# SCH_AC400-Controller_2024-03-15.net
KiCad netlist of a schematic drawn in EasyEDA
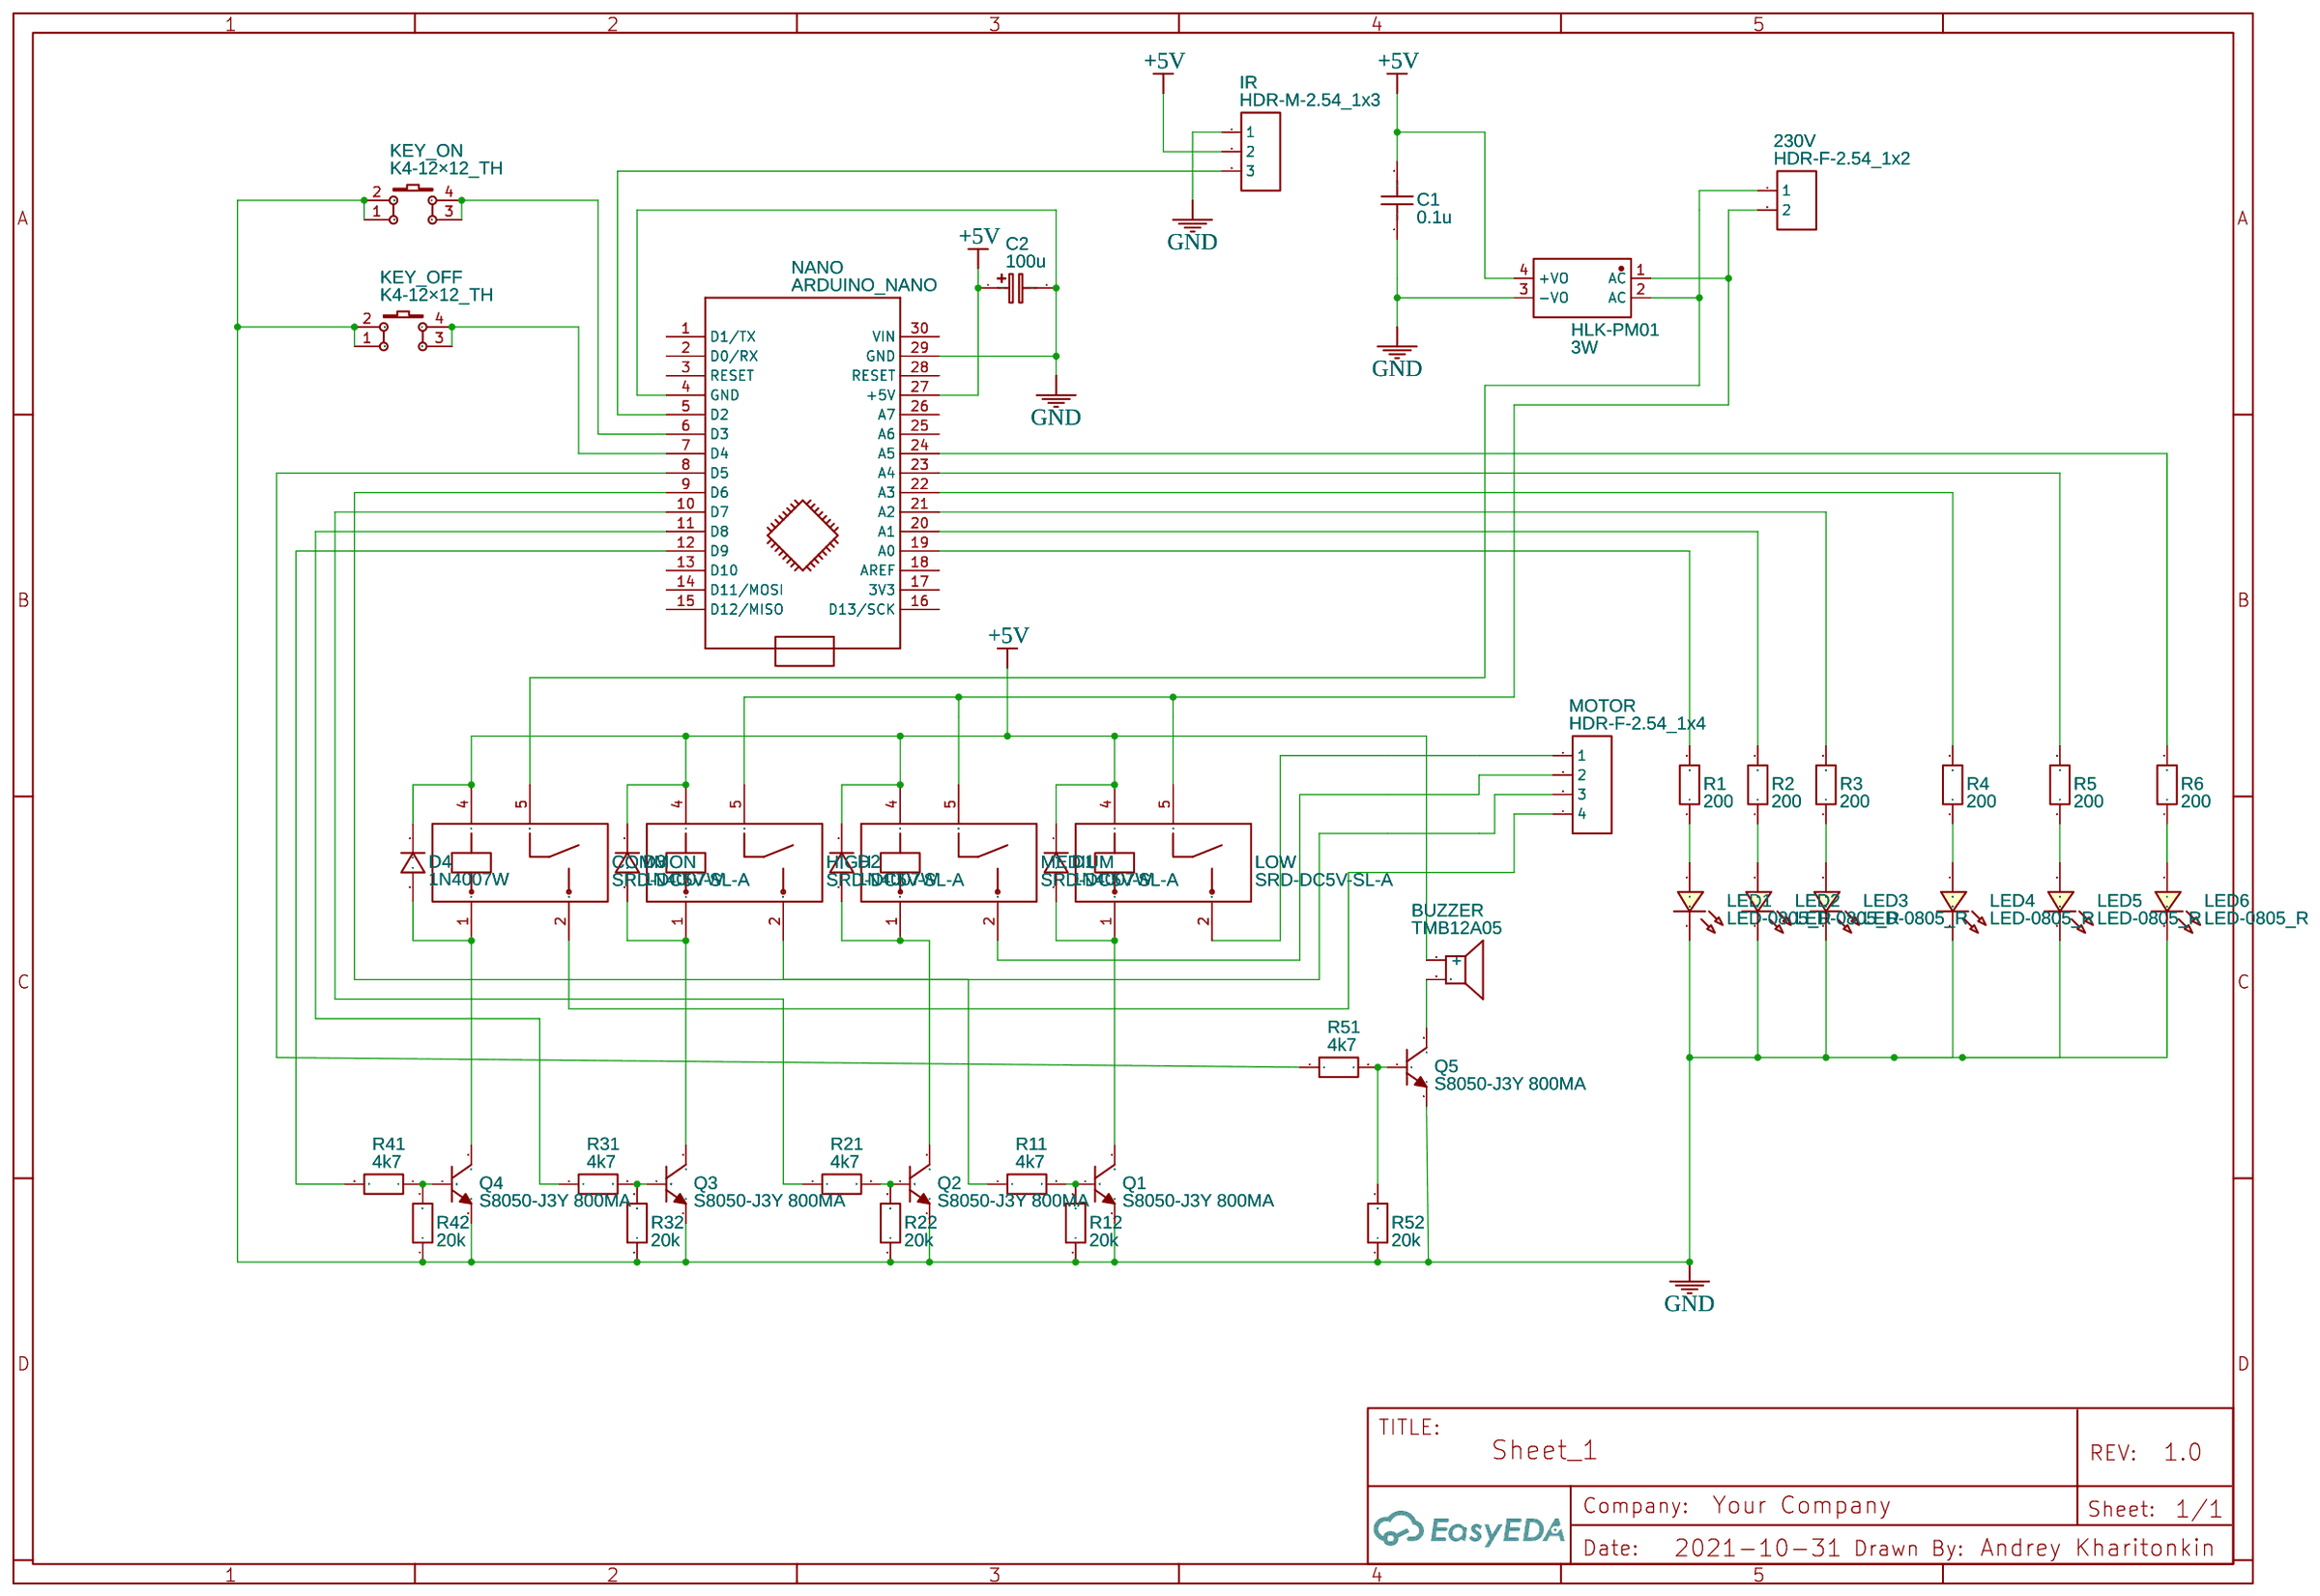
[diagram p0: schematic sheet]

(export (version "E")
  (design (tool "Eeschema 10.0.6"))
  (components
    (comp (ref "3W")
      (value "HLK-PM01")
      (fields (field (name "Manufacturer") "HI-LINK"))
      (libsource (lib "") (part "HLK-PM01"))
    )
    (comp (ref "230V") (value "HDR-F-2.54_1x2") (libsource (lib "") (part "HDR-F-2.54_1x2")))
    (comp (ref "BUZZER")
      (value "TMB12A05")
      (fields (field (name "Manufacturer") "HNDZ"))
      (libsource (lib "") (part "TMB12A05"))
    )
    (comp (ref "C1")
      (value "0.1u")
      (fields
        (field (name "Manufacturer Part") "CT41G-0805-2X1-50V-0.1uF-K(N)")
        (field (name "Manufacturer") "TORCH")
      )
      (libsource (lib "") (part "C_1206_US"))
    )
    (comp (ref "C2") (value "100u") (libsource (lib "") (part "CE_TH_D6.3×F2.5_EU")))
    (comp (ref "COMMON")
      (value "SRD-DC5V-SL-A")
      (fields (field (name "Manufacturer") "Ningbo Songle Relay"))
      (libsource (lib "") (part "SRD-DC5V-SL-A"))
    )
    (comp (ref "D1")
      (value "1N4007W")
      (fields (field (name "Manufacturer") "BLUE ROCKET"))
      (libsource (lib "") (part "1N4007W"))
    )
    (comp (ref "D2")
      (value "1N4007W")
      (fields (field (name "Manufacturer") "BLUE ROCKET"))
      (libsource (lib "") (part "1N4007W"))
    )
    (comp (ref "D3")
      (value "1N4007W")
      (fields (field (name "Manufacturer") "BLUE ROCKET"))
      (libsource (lib "") (part "1N4007W"))
    )
    (comp (ref "D4")
      (value "1N4007W")
      (fields (field (name "Manufacturer") "BLUE ROCKET"))
      (libsource (lib "") (part "1N4007W"))
    )
    (comp (ref "HIGH")
      (value "SRD-DC5V-SL-A")
      (fields (field (name "Manufacturer") "Ningbo Songle Relay"))
      (libsource (lib "") (part "SRD-DC5V-SL-A_1"))
    )
    (comp (ref "IR") (value "HDR-M-2.54_1x3") (libsource (lib "") (part "HDR-M-2.54_1x3")))
    (comp (ref "KEY_OFF")
      (value "K4-12×12_TH")
      (fields (field (name "Manufacturer Part") "K2-1103DP-M4SW-04") (field (name "Manufacturer") "韩国韩荣"))
      (libsource (lib "") (part "K4-12×12_TH"))
    )
    (comp (ref "KEY_ON")
      (value "K4-12×12_TH")
      (fields (field (name "Manufacturer Part") "K2-1103DP-M4SW-04") (field (name "Manufacturer") "韩国韩荣"))
      (libsource (lib "") (part "K4-12×12_TH_1"))
    )
    (comp (ref "LED1")
      (value "LED-0805_R")
      (fields
        (field (name "Manufacturer Part") "17-21SURC/S530-A3/TR8")
        (field (name "Manufacturer") "EVERLIGHT(台湾亿光)")
      )
      (libsource (lib "") (part "LED-0805_R"))
    )
    (comp (ref "LED2")
      (value "LED-0805_R")
      (fields
        (field (name "Manufacturer Part") "17-21SURC/S530-A3/TR8")
        (field (name "Manufacturer") "EVERLIGHT(台湾亿光)")
      )
      (libsource (lib "") (part "LED-0805_R"))
    )
    (comp (ref "LED3")
      (value "LED-0805_R")
      (fields
        (field (name "Manufacturer Part") "17-21SURC/S530-A3/TR8")
        (field (name "Manufacturer") "EVERLIGHT(台湾亿光)")
      )
      (libsource (lib "") (part "LED-0805_R"))
    )
    (comp (ref "LED4")
      (value "LED-0805_R")
      (fields
        (field (name "Manufacturer Part") "17-21SURC/S530-A3/TR8")
        (field (name "Manufacturer") "EVERLIGHT(台湾亿光)")
      )
      (libsource (lib "") (part "LED-0805_R"))
    )
    (comp (ref "LED5")
      (value "LED-0805_R")
      (fields
        (field (name "Manufacturer Part") "17-21SURC/S530-A3/TR8")
        (field (name "Manufacturer") "EVERLIGHT(台湾亿光)")
      )
      (libsource (lib "") (part "LED-0805_R"))
    )
    (comp (ref "LED6")
      (value "LED-0805_R")
      (fields
        (field (name "Manufacturer Part") "17-21SURC/S530-A3/TR8")
        (field (name "Manufacturer") "EVERLIGHT(台湾亿光)")
      )
      (libsource (lib "") (part "LED-0805_R"))
    )
    (comp (ref "LOW")
      (value "SRD-DC5V-SL-A")
      (fields (field (name "Manufacturer") "Ningbo Songle Relay"))
      (libsource (lib "") (part "SRD-DC5V-SL-A_2"))
    )
    (comp (ref "MEDIUM")
      (value "SRD-DC5V-SL-A")
      (fields (field (name "Manufacturer") "Ningbo Songle Relay"))
      (libsource (lib "") (part "SRD-DC5V-SL-A_3"))
    )
    (comp (ref "MOTOR") (value "HDR-F-2.54_1x4") (libsource (lib "") (part "HDR-F-2.54_1x4")))
    (comp (ref "NANO")
      (value "ARDUINO_NANO")
      (fields (field (name "Manufacturer Part") "?"))
      (libsource (lib "") (part "Unknown_405_-570"))
    )
    (comp (ref "Q1")
      (value "S8050-J3Y 800MA")
      (fields (field (name "Manufacturer") "IDCHIP(英锐芯)"))
      (libsource (lib "") (part "S8050-J3Y 800MA"))
    )
    (comp (ref "Q2")
      (value "S8050-J3Y 800MA")
      (fields (field (name "Manufacturer") "IDCHIP(英锐芯)"))
      (libsource (lib "") (part "S8050-J3Y 800MA"))
    )
    (comp (ref "Q3")
      (value "S8050-J3Y 800MA")
      (fields (field (name "Manufacturer") "IDCHIP(英锐芯)"))
      (libsource (lib "") (part "S8050-J3Y 800MA"))
    )
    (comp (ref "Q4")
      (value "S8050-J3Y 800MA")
      (fields (field (name "Manufacturer") "IDCHIP(英锐芯)"))
      (libsource (lib "") (part "S8050-J3Y 800MA"))
    )
    (comp (ref "Q5")
      (value "S8050-J3Y 800MA")
      (fields (field (name "Manufacturer") "IDCHIP(英锐芯)"))
      (libsource (lib "") (part "S8050-J3Y 800MA"))
    )
    (comp (ref "R1")
      (value "200")
      (fields (field (name "Manufacturer Part") "0805W8F2000T5E") (field (name "Manufacturer") "UniOhm"))
      (libsource (lib "") (part "R_0805_EU_1"))
    )
    (comp (ref "R2")
      (value "200")
      (fields (field (name "Manufacturer Part") "0805W8F2000T5E") (field (name "Manufacturer") "UniOhm"))
      (libsource (lib "") (part "R_0805_EU_1"))
    )
    (comp (ref "R3")
      (value "200")
      (fields (field (name "Manufacturer Part") "0805W8F2000T5E") (field (name "Manufacturer") "UniOhm"))
      (libsource (lib "") (part "R_0805_EU_1"))
    )
    (comp (ref "R4")
      (value "200")
      (fields (field (name "Manufacturer Part") "0805W8F2000T5E") (field (name "Manufacturer") "UniOhm"))
      (libsource (lib "") (part "R_0805_EU_1"))
    )
    (comp (ref "R5")
      (value "200")
      (fields (field (name "Manufacturer Part") "0805W8F2000T5E") (field (name "Manufacturer") "UniOhm"))
      (libsource (lib "") (part "R_0805_EU_1"))
    )
    (comp (ref "R6")
      (value "200")
      (fields (field (name "Manufacturer Part") "0805W8F2000T5E") (field (name "Manufacturer") "UniOhm"))
      (libsource (lib "") (part "R_0805_EU_1"))
    )
    (comp (ref "R11") (value "4k7") (libsource (lib "") (part "R_0805_EU_2")))
    (comp (ref "R12") (value "20k") (libsource (lib "") (part "R_0805_EU_1")))
    (comp (ref "R21") (value "4k7") (libsource (lib "") (part "R_0805_EU_2")))
    (comp (ref "R22") (value "20k") (libsource (lib "") (part "R_0805_EU_1")))
    (comp (ref "R31") (value "4k7") (libsource (lib "") (part "R_0805_EU_2")))
    (comp (ref "R32") (value "20k") (libsource (lib "") (part "R_0805_EU_1")))
    (comp (ref "R41") (value "4k7") (libsource (lib "") (part "R_0805_EU")))
    (comp (ref "R42") (value "20k") (libsource (lib "") (part "R_0805_EU_1")))
    (comp (ref "R51") (value "4k7") (libsource (lib "") (part "R_0805_EU_2")))
    (comp (ref "R52") (value "20k") (libsource (lib "") (part "R_0805_EU_1")))
  )
  (nets
    (net (code "1") (name "+5V") (class "Default")
      (node (ref "3W") (pin "4") (pinfunction "+VO_4") (pintype "unspecified"))
      (node (ref "BUZZER") (pin "1") (pinfunction "+_1") (pintype "unspecified"))
      (node (ref "C1") (pin "2") (pinfunction "2_2") (pintype "unspecified"))
      (node (ref "C2") (pin "1") (pinfunction "1_1") (pintype "unspecified"))
      (node (ref "COMMON") (pin "4") (pinfunction "4_4") (pintype "input"))
      (node (ref "D1") (pin "1") (pinfunction "1_1") (pintype "unspecified"))
      (node (ref "D2") (pin "1") (pinfunction "1_1") (pintype "unspecified"))
      (node (ref "D3") (pin "1") (pinfunction "1_1") (pintype "unspecified"))
      (node (ref "D4") (pin "1") (pinfunction "1_1") (pintype "unspecified"))
      (node (ref "HIGH") (pin "4") (pinfunction "4_4") (pintype "input"))
      (node (ref "IR") (pin "2") (pinfunction "2_2") (pintype "input"))
      (node (ref "LOW") (pin "4") (pinfunction "4_4") (pintype "input"))
      (node (ref "MEDIUM") (pin "4") (pinfunction "4_4") (pintype "input"))
      (node (ref "NANO") (pin "27") (pinfunction "+5V_27") (pintype "unspecified"))
    )
    (net (code "2") (name "GND") (class "Default")
      (node (ref "3W") (pin "3") (pinfunction "-VO_3") (pintype "unspecified"))
      (node (ref "C1") (pin "1") (pinfunction "1_1") (pintype "unspecified"))
      (node (ref "C2") (pin "2") (pinfunction "2_2") (pintype "unspecified"))
      (node (ref "IR") (pin "1") (pinfunction "1_1") (pintype "input"))
      (node (ref "KEY_OFF") (pin "1") (pinfunction "1_1") (pintype "unspecified"))
      (node (ref "KEY_OFF") (pin "2") (pinfunction "2_2") (pintype "unspecified"))
      (node (ref "KEY_ON") (pin "1") (pinfunction "1_1") (pintype "unspecified"))
      (node (ref "KEY_ON") (pin "2") (pinfunction "2_2") (pintype "unspecified"))
      (node (ref "LED1") (pin "2") (pinfunction "2_2") (pintype "unspecified"))
      (node (ref "LED2") (pin "2") (pinfunction "2_2") (pintype "unspecified"))
      (node (ref "LED3") (pin "2") (pinfunction "2_2") (pintype "unspecified"))
      (node (ref "LED4") (pin "2") (pinfunction "2_2") (pintype "unspecified"))
      (node (ref "LED5") (pin "2") (pinfunction "2_2") (pintype "unspecified"))
      (node (ref "LED6") (pin "2") (pinfunction "2_2") (pintype "unspecified"))
      (node (ref "NANO") (pin "29") (pinfunction "GND_29") (pintype "unspecified"))
      (node (ref "NANO") (pin "4") (pinfunction "GND_4") (pintype "unspecified"))
      (node (ref "Q1") (pin "2") (pinfunction "E_2") (pintype "input"))
      (node (ref "Q2") (pin "2") (pinfunction "E_2") (pintype "input"))
      (node (ref "Q3") (pin "2") (pinfunction "E_2") (pintype "input"))
      (node (ref "Q4") (pin "2") (pinfunction "E_2") (pintype "input"))
      (node (ref "Q5") (pin "2") (pinfunction "E_2") (pintype "input"))
      (node (ref "R12") (pin "1") (pinfunction "1_1") (pintype "unspecified"))
      (node (ref "R22") (pin "1") (pinfunction "1_1") (pintype "unspecified"))
      (node (ref "R32") (pin "1") (pinfunction "1_1") (pintype "unspecified"))
      (node (ref "R42") (pin "1") (pinfunction "1_1") (pintype "unspecified"))
      (node (ref "R52") (pin "1") (pinfunction "1_1") (pintype "unspecified"))
    )
    (net (code "3") (name "Net-(230V-Pad1)") (class "Default")
      (node (ref "230V") (pin "1") (pinfunction "1_1") (pintype "input"))
      (node (ref "3W") (pin "2") (pinfunction "AC_2") (pintype "unspecified"))
      (node (ref "COMMON") (pin "5") (pinfunction "5_5") (pintype "input"))
    )
    (net (code "4") (name "Net-(230V-Pad2)") (class "Default")
      (node (ref "230V") (pin "2") (pinfunction "2_2") (pintype "input"))
      (node (ref "3W") (pin "1") (pinfunction "AC_1") (pintype "unspecified"))
      (node (ref "HIGH") (pin "5") (pinfunction "5_5") (pintype "input"))
      (node (ref "LOW") (pin "5") (pinfunction "5_5") (pintype "input"))
      (node (ref "MEDIUM") (pin "5") (pinfunction "5_5") (pintype "input"))
    )
    (net (code "5") (name "Net-(COMMON-Pad2)") (class "Default")
      (node (ref "COMMON") (pin "2") (pinfunction "2_2") (pintype "input"))
      (node (ref "MOTOR") (pin "4") (pinfunction "4_4") (pintype "unspecified"))
    )
    (net (code "6") (name "Net-(HIGH-Pad2)") (class "Default")
      (node (ref "HIGH") (pin "2") (pinfunction "2_2") (pintype "input"))
      (node (ref "MOTOR") (pin "3") (pinfunction "3_3") (pintype "unspecified"))
    )
    (net (code "7") (name "Net-(LED1-Pad1)") (class "Default")
      (node (ref "LED1") (pin "1") (pinfunction "1_1") (pintype "unspecified"))
      (node (ref "R1") (pin "1") (pinfunction "1_1") (pintype "unspecified"))
    )
    (net (code "8") (name "Net-(LED2-Pad1)") (class "Default")
      (node (ref "LED2") (pin "1") (pinfunction "1_1") (pintype "unspecified"))
      (node (ref "R2") (pin "1") (pinfunction "1_1") (pintype "unspecified"))
    )
    (net (code "9") (name "Net-(LED3-Pad1)") (class "Default")
      (node (ref "LED3") (pin "1") (pinfunction "1_1") (pintype "unspecified"))
      (node (ref "R3") (pin "1") (pinfunction "1_1") (pintype "unspecified"))
    )
    (net (code "10") (name "Net-(LED4-Pad1)") (class "Default")
      (node (ref "LED4") (pin "1") (pinfunction "1_1") (pintype "unspecified"))
      (node (ref "R4") (pin "1") (pinfunction "1_1") (pintype "unspecified"))
    )
    (net (code "11") (name "Net-(LED5-Pad1)") (class "Default")
      (node (ref "LED5") (pin "1") (pinfunction "1_1") (pintype "unspecified"))
      (node (ref "R5") (pin "1") (pinfunction "1_1") (pintype "unspecified"))
    )
    (net (code "12") (name "Net-(LED6-Pad1)") (class "Default")
      (node (ref "LED6") (pin "1") (pinfunction "1_1") (pintype "unspecified"))
      (node (ref "R6") (pin "1") (pinfunction "1_1") (pintype "unspecified"))
    )
    (net (code "13") (name "Net-(LOW-Pad2)") (class "Default")
      (node (ref "LOW") (pin "2") (pinfunction "2_2") (pintype "input"))
      (node (ref "MOTOR") (pin "1") (pinfunction "1_1") (pintype "unspecified"))
    )
    (net (code "14") (name "Net-(MEDIUM-Pad2)") (class "Default")
      (node (ref "MEDIUM") (pin "2") (pinfunction "2_2") (pintype "input"))
      (node (ref "MOTOR") (pin "2") (pinfunction "2_2") (pintype "unspecified"))
    )
    (net (code "15") (name "Net-(NANO-A0)") (class "Default")
      (node (ref "NANO") (pin "19") (pinfunction "A0_19") (pintype "unspecified"))
      (node (ref "R1") (pin "2") (pinfunction "2_2") (pintype "unspecified"))
    )
    (net (code "16") (name "Net-(NANO-A1)") (class "Default")
      (node (ref "NANO") (pin "20") (pinfunction "A1_20") (pintype "unspecified"))
      (node (ref "R2") (pin "2") (pinfunction "2_2") (pintype "unspecified"))
    )
    (net (code "17") (name "Net-(NANO-A2)") (class "Default")
      (node (ref "NANO") (pin "21") (pinfunction "A2_21") (pintype "unspecified"))
      (node (ref "R3") (pin "2") (pinfunction "2_2") (pintype "unspecified"))
    )
    (net (code "18") (name "Net-(NANO-A3)") (class "Default")
      (node (ref "NANO") (pin "22") (pinfunction "A3_22") (pintype "unspecified"))
      (node (ref "R4") (pin "2") (pinfunction "2_2") (pintype "unspecified"))
    )
    (net (code "19") (name "Net-(NANO-A4)") (class "Default")
      (node (ref "NANO") (pin "23") (pinfunction "A4_23") (pintype "unspecified"))
      (node (ref "R5") (pin "2") (pinfunction "2_2") (pintype "unspecified"))
    )
    (net (code "20") (name "Net-(NANO-A5)") (class "Default")
      (node (ref "NANO") (pin "24") (pinfunction "A5_24") (pintype "unspecified"))
      (node (ref "R6") (pin "2") (pinfunction "2_2") (pintype "unspecified"))
    )
    (net (code "21") (name "Net-(NANO-D2)") (class "Default")
      (node (ref "IR") (pin "3") (pinfunction "3_3") (pintype "input"))
      (node (ref "NANO") (pin "5") (pinfunction "D2_5") (pintype "unspecified"))
    )
    (net (code "22") (name "Net-(NANO-D3)") (class "Default")
      (node (ref "KEY_ON") (pin "3") (pinfunction "3_3") (pintype "unspecified"))
      (node (ref "KEY_ON") (pin "4") (pinfunction "4_4") (pintype "unspecified"))
      (node (ref "NANO") (pin "6") (pinfunction "D3_6") (pintype "unspecified"))
    )
    (net (code "23") (name "Net-(NANO-D4)") (class "Default")
      (node (ref "KEY_OFF") (pin "3") (pinfunction "3_3") (pintype "unspecified"))
      (node (ref "KEY_OFF") (pin "4") (pinfunction "4_4") (pintype "unspecified"))
      (node (ref "NANO") (pin "7") (pinfunction "D4_7") (pintype "unspecified"))
    )
    (net (code "24") (name "Net-(NANO-D5)") (class "Default")
      (node (ref "NANO") (pin "8") (pinfunction "D5_8") (pintype "unspecified"))
      (node (ref "R51") (pin "1") (pinfunction "1_1") (pintype "unspecified"))
    )
    (net (code "25") (name "Net-(NANO-D6)") (class "Default")
      (node (ref "NANO") (pin "9") (pinfunction "D6_9") (pintype "unspecified"))
      (node (ref "R11") (pin "1") (pinfunction "1_1") (pintype "unspecified"))
    )
    (net (code "26") (name "Net-(NANO-D7)") (class "Default")
      (node (ref "NANO") (pin "10") (pinfunction "D7_10") (pintype "unspecified"))
      (node (ref "R21") (pin "1") (pinfunction "1_1") (pintype "unspecified"))
    )
    (net (code "27") (name "Net-(NANO-D8)") (class "Default")
      (node (ref "NANO") (pin "11") (pinfunction "D8_11") (pintype "unspecified"))
      (node (ref "R31") (pin "1") (pinfunction "1_1") (pintype "unspecified"))
    )
    (net (code "28") (name "Net-(NANO-D9)") (class "Default")
      (node (ref "NANO") (pin "12") (pinfunction "D9_12") (pintype "unspecified"))
      (node (ref "R41") (pin "2") (pinfunction "2_2") (pintype "unspecified"))
    )
    (net (code "29") (name "Net-(Q1-B)") (class "Default")
      (node (ref "Q1") (pin "1") (pinfunction "B_1") (pintype "input"))
      (node (ref "R11") (pin "2") (pinfunction "2_2") (pintype "unspecified"))
      (node (ref "R12") (pin "2") (pinfunction "2_2") (pintype "unspecified"))
    )
    (net (code "30") (name "Net-(Q1-C)") (class "Default")
      (node (ref "D1") (pin "2") (pinfunction "2_2") (pintype "unspecified"))
      (node (ref "LOW") (pin "1") (pinfunction "1_1") (pintype "input"))
      (node (ref "Q1") (pin "3") (pinfunction "C_3") (pintype "input"))
    )
    (net (code "31") (name "Net-(Q2-B)") (class "Default")
      (node (ref "Q2") (pin "1") (pinfunction "B_1") (pintype "input"))
      (node (ref "R21") (pin "2") (pinfunction "2_2") (pintype "unspecified"))
      (node (ref "R22") (pin "2") (pinfunction "2_2") (pintype "unspecified"))
    )
    (net (code "32") (name "Net-(Q2-C)") (class "Default")
      (node (ref "D2") (pin "2") (pinfunction "2_2") (pintype "unspecified"))
      (node (ref "MEDIUM") (pin "1") (pinfunction "1_1") (pintype "input"))
      (node (ref "Q2") (pin "3") (pinfunction "C_3") (pintype "input"))
    )
    (net (code "33") (name "Net-(Q3-B)") (class "Default")
      (node (ref "Q3") (pin "1") (pinfunction "B_1") (pintype "input"))
      (node (ref "R31") (pin "2") (pinfunction "2_2") (pintype "unspecified"))
      (node (ref "R32") (pin "2") (pinfunction "2_2") (pintype "unspecified"))
    )
    (net (code "34") (name "Net-(Q3-C)") (class "Default")
      (node (ref "D3") (pin "2") (pinfunction "2_2") (pintype "unspecified"))
      (node (ref "HIGH") (pin "1") (pinfunction "1_1") (pintype "input"))
      (node (ref "Q3") (pin "3") (pinfunction "C_3") (pintype "input"))
    )
    (net (code "35") (name "Net-(Q4-B)") (class "Default")
      (node (ref "Q4") (pin "1") (pinfunction "B_1") (pintype "input"))
      (node (ref "R41") (pin "1") (pinfunction "1_1") (pintype "unspecified"))
      (node (ref "R42") (pin "2") (pinfunction "2_2") (pintype "unspecified"))
    )
    (net (code "36") (name "Net-(Q4-C)") (class "Default")
      (node (ref "COMMON") (pin "1") (pinfunction "1_1") (pintype "input"))
      (node (ref "D4") (pin "2") (pinfunction "2_2") (pintype "unspecified"))
      (node (ref "Q4") (pin "3") (pinfunction "C_3") (pintype "input"))
    )
    (net (code "37") (name "Net-(Q5-B)") (class "Default")
      (node (ref "Q5") (pin "1") (pinfunction "B_1") (pintype "input"))
      (node (ref "R51") (pin "2") (pinfunction "2_2") (pintype "unspecified"))
      (node (ref "R52") (pin "2") (pinfunction "2_2") (pintype "unspecified"))
    )
    (net (code "38") (name "Net-(Q5-C)") (class "Default")
      (node (ref "BUZZER") (pin "2") (pinfunction "2_2") (pintype "unspecified"))
      (node (ref "Q5") (pin "3") (pinfunction "C_3") (pintype "input"))
    )
    (net (code "39") (name "unconnected-(NANO-3V3-Pad17)") (class "Default")
      (node (ref "NANO") (pin "17") (pinfunction "3V3_17") (pintype "unspecified"))
    )
    (net (code "40") (name "unconnected-(NANO-A6-Pad25)") (class "Default")
      (node (ref "NANO") (pin "25") (pinfunction "A6_25") (pintype "unspecified"))
    )
    (net (code "41") (name "unconnected-(NANO-A7-Pad26)") (class "Default")
      (node (ref "NANO") (pin "26") (pinfunction "A7_26") (pintype "unspecified"))
    )
    (net (code "42") (name "unconnected-(NANO-AREF-Pad18)") (class "Default")
      (node (ref "NANO") (pin "18") (pinfunction "AREF_18") (pintype "unspecified"))
    )
    (net (code "43") (name "unconnected-(NANO-D0{slash}RX-Pad2)") (class "Default")
      (node (ref "NANO") (pin "2") (pinfunction "D0/RX_2") (pintype "unspecified"))
    )
    (net (code "44") (name "unconnected-(NANO-D1{slash}TX-Pad1)") (class "Default")
      (node (ref "NANO") (pin "1") (pinfunction "D1/TX_1") (pintype "unspecified"))
    )
    (net (code "45") (name "unconnected-(NANO-D10-Pad13)") (class "Default")
      (node (ref "NANO") (pin "13") (pinfunction "D10_13") (pintype "unspecified"))
    )
    (net (code "46") (name "unconnected-(NANO-D11{slash}MOSI-Pad14)") (class "Default")
      (node (ref "NANO") (pin "14") (pinfunction "D11/MOSI_14") (pintype "unspecified"))
    )
    (net (code "47") (name "unconnected-(NANO-D12{slash}MISO-Pad15)") (class "Default")
      (node (ref "NANO") (pin "15") (pinfunction "D12/MISO_15") (pintype "unspecified"))
    )
    (net (code "48") (name "unconnected-(NANO-D13{slash}SCK-Pad16)") (class "Default")
      (node (ref "NANO") (pin "16") (pinfunction "D13/SCK_16") (pintype "unspecified"))
    )
    (net (code "49") (name "unconnected-(NANO-RESET-Pad3)") (class "Default")
      (node (ref "NANO") (pin "3") (pinfunction "RESET_3") (pintype "unspecified"))
    )
    (net (code "50") (name "unconnected-(NANO-RESET-Pad28)") (class "Default")
      (node (ref "NANO") (pin "28") (pinfunction "RESET_28") (pintype "unspecified"))
    )
    (net (code "51") (name "unconnected-(NANO-VIN-Pad30)") (class "Default")
      (node (ref "NANO") (pin "30") (pinfunction "VIN_30") (pintype "unspecified"))
    )
  )
)
